# Connections.net
KiCad netlist of a schematic drawn in Altium Designer
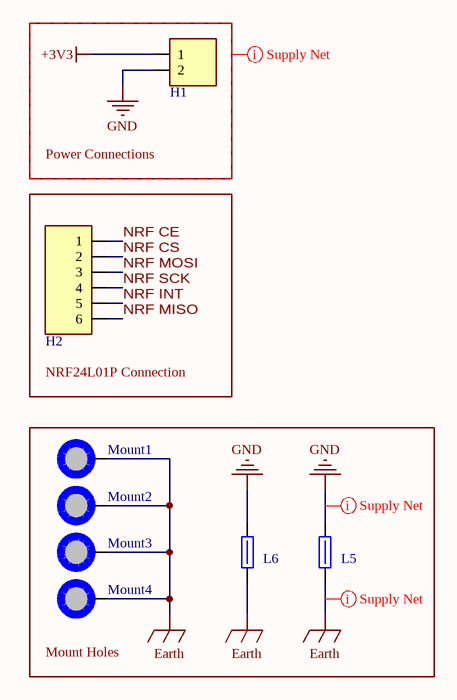
[diagram p0: Connections.SchDoc]

(export (version "E")
  (design (tool "Eeschema 10.0.6"))
  (components
    (comp (ref "H1")
      (value "1x2 Male")
      (footprint "[Header] Shrouded 1x2 Male")
      (description "0705430036\r\nMates with 0050579402")
      (libsource (lib "RADM Connectors") (part "[Header] Shrouded 1x2 Male"))
    )
    (comp (ref "H2")
      (value "[Header] Shrouded 1x6 Male")
      (footprint "[Header] Shrouded 1x6 Male")
      (description "0705430005\r\nMates with 0050579406")
      (libsource (lib "RADM Connectors") (part "[Header] Shrouded 1x6 Male"))
    )
    (comp (ref "L5")
      (value "652-MH2029-300Y")
      (footprint "[Ferrite] SMD Bead 0805 (1)")
      (libsource (lib "RADM Components") (part "[Ferrite] SMD Ferrite Bead (1)"))
    )
    (comp (ref "L6")
      (value "652-MH2029-300Y")
      (footprint "[Ferrite] SMD Bead 0805 (1)")
      (libsource (lib "RADM Components") (part "[Ferrite] SMD Ferrite Bead (1)"))
    )
    (comp (ref "Mount1")
      (value "M3 Mount Hole")
      (footprint "[Mount] M3 Mount Hole")
      (description "Place at least 4.5mm from board edge. Plated.")
      (libsource (lib "RADM Connectors") (part "[Mount] M3 Mount Hole"))
    )
    (comp (ref "Mount2")
      (value "M3 Mount Hole")
      (footprint "[Mount] M3 Mount Hole")
      (description "Place at least 4.5mm from board edge. Plated.")
      (libsource (lib "RADM Connectors") (part "[Mount] M3 Mount Hole"))
    )
    (comp (ref "Mount3")
      (value "M3 Mount Hole")
      (footprint "[Mount] M3 Mount Hole")
      (description "Place at least 4.5mm from board edge. Plated.")
      (libsource (lib "RADM Connectors") (part "[Mount] M3 Mount Hole"))
    )
    (comp (ref "Mount4")
      (value "M3 Mount Hole")
      (footprint "[Mount] M3 Mount Hole")
      (description "Place at least 4.5mm from board edge. Plated.")
      (libsource (lib "RADM Connectors") (part "[Mount] M3 Mount Hole"))
    )
  )
  (nets
    (net (code "1") (name "+3V3") (class "Default")
      (node (ref "H1") (pin "1") (pinfunction "1_1") (pintype "passive"))
    )
    (net (code "2") (name "/NRF CE") (class "Default")
      (node (ref "H2") (pin "1") (pinfunction "1_1") (pintype "passive"))
    )
    (net (code "3") (name "/NRF CS") (class "Default")
      (node (ref "H2") (pin "2") (pinfunction "2_2") (pintype "passive"))
    )
    (net (code "4") (name "/NRF INT") (class "Default")
      (node (ref "H2") (pin "5") (pinfunction "5_5") (pintype "passive"))
    )
    (net (code "5") (name "/NRF MISO") (class "Default")
      (node (ref "H2") (pin "6") (pinfunction "6_6") (pintype "passive"))
    )
    (net (code "6") (name "/NRF MOSI") (class "Default")
      (node (ref "H2") (pin "3") (pinfunction "3_3") (pintype "passive"))
    )
    (net (code "7") (name "/NRF SCK") (class "Default")
      (node (ref "H2") (pin "4") (pinfunction "4_4") (pintype "passive"))
    )
    (net (code "8") (name "Earth") (class "Default")
      (node (ref "L5") (pin "1") (pinfunction "1_1") (pintype "passive"))
      (node (ref "L6") (pin "1") (pinfunction "1_1") (pintype "passive"))
      (node (ref "Mount1") (pin "1") (pintype "power_in"))
      (node (ref "Mount2") (pin "1") (pintype "power_in"))
      (node (ref "Mount3") (pin "1") (pintype "power_in"))
      (node (ref "Mount4") (pin "1") (pintype "power_in"))
    )
    (net (code "9") (name "GND") (class "Default")
      (node (ref "H1") (pin "2") (pinfunction "2_2") (pintype "passive"))
      (node (ref "L5") (pin "2") (pinfunction "2_2") (pintype "passive"))
      (node (ref "L6") (pin "2") (pinfunction "2_2") (pintype "passive"))
    )
  )
)
